# Power.net
KiCad netlist of a schematic drawn in Altium Designer
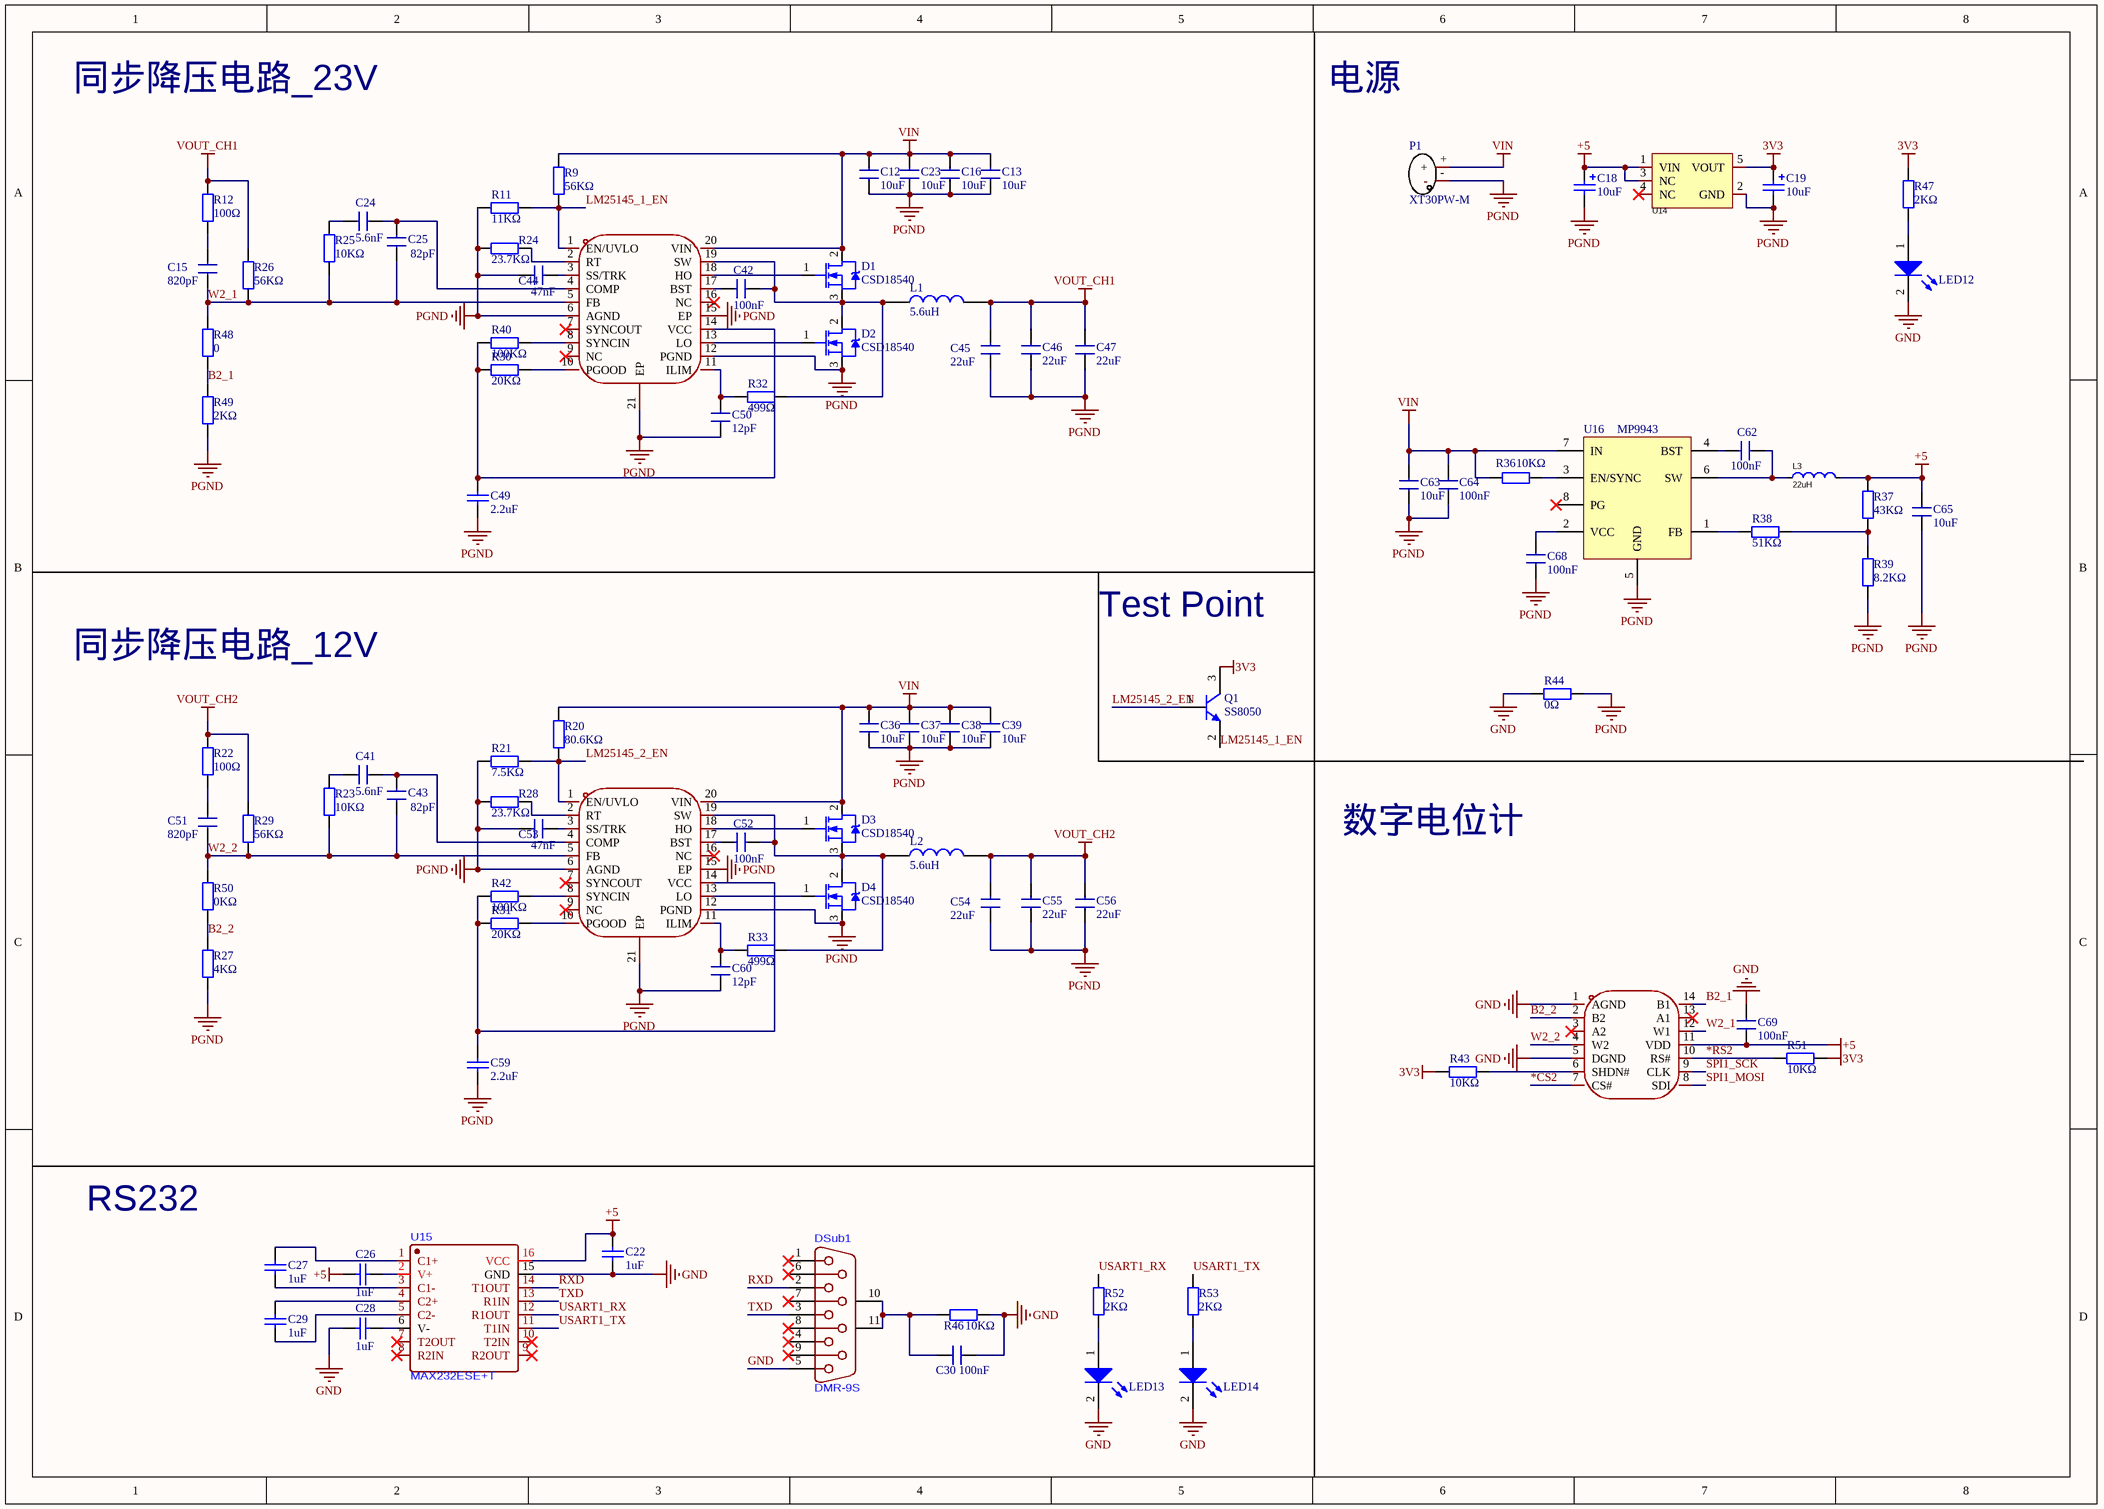
[diagram p0: Power.SchDoc]

(export (version "E")
  (design (tool "Eeschema 10.0.6"))
  (components
    (comp (ref "C12")
      (value "10uF")
      (footprint "1210")
      (description "1210贴片电容")
      (libsource (lib "Integrated_Library1") (part "1210贴片电容"))
    )
    (comp (ref "C13")
      (value "10uF")
      (footprint "1210")
      (description "1210贴片电容")
      (libsource (lib "En") (part "1210贴片电容"))
    )
    (comp (ref "C15")
      (value "820pF")
      (footprint "c0402")
      (description "贴片电容0402")
      (libsource (lib "Integrated_Library1") (part "0402贴片电容"))
    )
    (comp (ref "C16")
      (value "10uF")
      (footprint "1210")
      (description "1210贴片电容")
      (libsource (lib "En") (part "1210贴片电容"))
    )
    (comp (ref "C18")
      (value "10uF")
      (footprint "3216")
      (description "3216钽电容")
      (libsource (lib "Integrated_Library1") (part "3216钽电容"))
    )
    (comp (ref "C19")
      (value "10uF")
      (footprint "3216")
      (description "3216钽电容")
      (libsource (lib "Integrated_Library1") (part "3216钽电容"))
    )
    (comp (ref "C22")
      (value "1uF")
      (footprint "C 0603_M")
      (description "0603贴片电容")
      (libsource (lib "En") (part "0603贴片电容"))
    )
    (comp (ref "C23")
      (value "10uF")
      (footprint "1210")
      (description "1210贴片电容")
      (libsource (lib "En") (part "1210贴片电容"))
    )
    (comp (ref "C24")
      (value "5.6nF")
      (footprint "c0402")
      (description "贴片电容0402")
      (libsource (lib "Integrated_Library1") (part "0402贴片电容"))
    )
    (comp (ref "C25")
      (value "82pF")
      (footprint "c0402")
      (description "贴片电容0402")
      (libsource (lib "Integrated_Library1") (part "0402贴片电容"))
    )
    (comp (ref "C26")
      (value "1uF")
      (footprint "C 0603_M")
      (description "0603贴片电容")
      (libsource (lib "En") (part "0603贴片电容"))
    )
    (comp (ref "C27")
      (value "1uF")
      (footprint "C 0603_M")
      (description "0603贴片电容")
      (libsource (lib "En") (part "0603贴片电容"))
    )
    (comp (ref "C28")
      (value "1uF")
      (footprint "C 0603_M")
      (description "0603贴片电容")
      (libsource (lib "En") (part "0603贴片电容"))
    )
    (comp (ref "C29")
      (value "1uF")
      (footprint "C 0603_M")
      (description "0603贴片电容")
      (libsource (lib "En") (part "0603贴片电容"))
    )
    (comp (ref "C30")
      (value "100nF")
      (footprint "c0402")
      (description "贴片电容0402")
      (libsource (lib "Integrated_Library1") (part "0402贴片电容"))
    )
    (comp (ref "C36")
      (value "10uF")
      (footprint "1210")
      (description "1210贴片电容")
      (libsource (lib "Integrated_Library1") (part "1210贴片电容"))
    )
    (comp (ref "C37")
      (value "10uF")
      (footprint "1210")
      (description "1210贴片电容")
      (libsource (lib "En") (part "1210贴片电容"))
    )
    (comp (ref "C38")
      (value "10uF")
      (footprint "1210")
      (description "1210贴片电容")
      (libsource (lib "En") (part "1210贴片电容"))
    )
    (comp (ref "C39")
      (value "10uF")
      (footprint "1210")
      (description "1210贴片电容")
      (libsource (lib "En") (part "1210贴片电容"))
    )
    (comp (ref "C41")
      (value "5.6nF")
      (footprint "c0402")
      (description "贴片电容0402")
      (libsource (lib "Integrated_Library1") (part "0402贴片电容"))
    )
    (comp (ref "C42")
      (value "100nF")
      (footprint "C 0603_M")
      (description "贴片电容0402")
      (libsource (lib "Integrated_Library1") (part "0402贴片电容"))
    )
    (comp (ref "C43")
      (value "82pF")
      (footprint "c0402")
      (description "贴片电容0402")
      (libsource (lib "Integrated_Library1") (part "0402贴片电容"))
    )
    (comp (ref "C44")
      (value "47nF")
      (footprint "c0402")
      (description "贴片电容0402")
      (libsource (lib "Integrated_Library1") (part "0402贴片电容"))
    )
    (comp (ref "C45")
      (value "22uF")
      (footprint "1210")
      (description "1210贴片电容")
      (libsource (lib "En") (part "1210贴片电容"))
    )
    (comp (ref "C46")
      (value "22uF")
      (footprint "1210")
      (description "1210贴片电容")
      (libsource (lib "En") (part "1210贴片电容"))
    )
    (comp (ref "C47")
      (value "22uF")
      (footprint "1210")
      (description "1210贴片电容")
      (libsource (lib "En") (part "1210贴片电容"))
    )
    (comp (ref "C49")
      (value "2.2uF")
      (footprint "C 0603_M")
      (description "0603贴片电容")
      (libsource (lib "En") (part "0603贴片电容"))
    )
    (comp (ref "C50")
      (value "12pF")
      (footprint "c0402")
      (description "贴片电容0402")
      (libsource (lib "Integrated_Library1") (part "0402贴片电容"))
    )
    (comp (ref "C51")
      (value "820pF")
      (footprint "c0402")
      (description "贴片电容0402")
      (libsource (lib "Integrated_Library1") (part "0402贴片电容"))
    )
    (comp (ref "C52")
      (value "100nF")
      (footprint "C 0603_M")
      (description "贴片电容0402")
      (libsource (lib "Integrated_Library1") (part "0402贴片电容"))
    )
    (comp (ref "C53")
      (value "47nF")
      (footprint "c0402")
      (description "贴片电容0402")
      (libsource (lib "Integrated_Library1") (part "0402贴片电容"))
    )
    (comp (ref "C54")
      (value "22uF")
      (footprint "1210")
      (description "1210贴片电容")
      (libsource (lib "En") (part "1210贴片电容"))
    )
    (comp (ref "C55")
      (value "22uF")
      (footprint "1210")
      (description "1210贴片电容")
      (libsource (lib "En") (part "1210贴片电容"))
    )
    (comp (ref "C56")
      (value "22uF")
      (footprint "1210")
      (description "1210贴片电容")
      (libsource (lib "En") (part "1210贴片电容"))
    )
    (comp (ref "C59")
      (value "2.2uF")
      (footprint "C 0603_M")
      (description "0603贴片电容")
      (libsource (lib "En") (part "0603贴片电容"))
    )
    (comp (ref "C60")
      (value "12pF")
      (footprint "c0402")
      (description "贴片电容0402")
      (libsource (lib "Integrated_Library1") (part "0402贴片电容"))
    )
    (comp (ref "C62")
      (value "100nF")
      (footprint "c0402")
      (description "贴片电容0402")
      (libsource (lib "Integrated_Library1") (part "0402贴片电容"))
    )
    (comp (ref "C63")
      (value "10uF")
      (footprint "1210")
      (description "1210贴片电容")
      (libsource (lib "Integrated_Library1") (part "1210贴片电容"))
    )
    (comp (ref "C64")
      (value "100nF")
      (footprint "c0402")
      (description "贴片电容0402")
      (libsource (lib "Integrated_Library1") (part "0402贴片电容"))
    )
    (comp (ref "C65")
      (value "10uF")
      (footprint "1210")
      (description "1210贴片电容")
      (libsource (lib "Integrated_Library1") (part "1210贴片电容"))
    )
    (comp (ref "C68")
      (value "100nF")
      (footprint "c0402")
      (description "贴片电容0402")
      (libsource (lib "Integrated_Library1") (part "0402贴片电容"))
    )
    (comp (ref "C69")
      (value "100nF")
      (footprint "c0402")
      (description "贴片电容0402")
      (libsource (lib "Integrated_Library1") (part "0402贴片电容"))
    )
    (comp (ref "D1")
      (value "CSD18540")
      (footprint "pg-tdson-8")
      (description "N沟道MOS管")
      (fields (field (name "PUBLISHER") "Altium Limited"))
      (libsource (lib "En") (part "CSD18540"))
    )
    (comp (ref "D2")
      (value "CSD18540")
      (footprint "pg-tdson-8")
      (description "N沟道MOS管")
      (fields (field (name "PUBLISHER") "Altium Limited"))
      (libsource (lib "En") (part "CSD18540"))
    )
    (comp (ref "D3")
      (value "CSD18540")
      (footprint "pg-tdson-8")
      (description "N沟道MOS管")
      (fields (field (name "PUBLISHER") "Altium Limited"))
      (libsource (lib "En") (part "CSD18540"))
    )
    (comp (ref "D4")
      (value "CSD18540")
      (footprint "pg-tdson-8")
      (description "N沟道MOS管")
      (fields (field (name "PUBLISHER") "Altium Limited"))
      (libsource (lib "En") (part "CSD18540"))
    )
    (comp (ref "DSub1")
      (value "DMR-9S")
      (footprint "DSUB-TH_DMR-9S")
      (libsource (lib "Schlib1") (part "DMR-9S"))
    )
    (comp (ref "L1")
      (value "5.6uH")
      (footprint "L-SMD-0630")
      (description "一体成型屏蔽电感")
      (libsource (lib "En") (part "0630功率电感"))
    )
    (comp (ref "L2")
      (value "5.6uH")
      (footprint "L-SMD-0630")
      (description "一体成型屏蔽电感")
      (libsource (lib "En") (part "0630功率电感"))
    )
    (comp (ref "L3")
      (value "22uH")
      (footprint "IND-SMD_L5.4-W5.2")
      (description "一体成型屏蔽电感，0530封装，额定电流3A")
      (fields (field (name "MANUFACTURER") "XR(祥如)") (field (name "MANUFACTURER PART") "XR0530-100M"))
      (libsource (lib "En") (part "0530屏蔽电感"))
    )
    (comp (ref "LED12")
      (value "LED")
      (footprint "led0805")
      (description "0805贴片LED")
      (libsource (lib "Integrated_Library1") (part "0805贴片LED"))
    )
    (comp (ref "LED13")
      (value "LED")
      (footprint "led0805")
      (description "0805贴片LED")
      (libsource (lib "Integrated_Library1") (part "0805贴片LED"))
    )
    (comp (ref "LED14")
      (value "LED")
      (footprint "led0805")
      (description "0805贴片LED")
      (libsource (lib "Integrated_Library1") (part "0805贴片LED"))
    )
    (comp (ref "P1")
      (value "XT30PW-M")
      (footprint "XT30PW-M")
      (description "卧式XT30母头")
      (fields (field (name "PUBLISHER") "Altium Limited"))
      (libsource (lib "Integrated_Library1") (part "卧式XT30母头"))
    )
    (comp (ref "Q1")
      (value "SS8050")
      (footprint "SOT-23-3_L2.9-W1.3-P1.90-LS2.4-BR")
      (description "三极管")
      (libsource (lib "Integrated_Library1") (part "2N2222"))
    )
    (comp (ref "R9")
      (value "56KΩ")
      (footprint "R0402")
      (description "0402贴片电阻")
      (libsource (lib "") (part "0402贴片电阻_3"))
    )
    (comp (ref "R11")
      (value "11KΩ")
      (footprint "R0402")
      (description "0402贴片电阻")
      (libsource (lib "") (part "0402贴片电阻_2"))
    )
    (comp (ref "R12")
      (value "100Ω")
      (footprint "R0402")
      (description "0402贴片电阻")
      (libsource (lib "") (part "0402贴片电阻_1"))
    )
    (comp (ref "R20")
      (value "80.6KΩ")
      (footprint "R0402")
      (description "0402贴片电阻")
      (libsource (lib "") (part "0402贴片电阻_3"))
    )
    (comp (ref "R21")
      (value "7.5KΩ")
      (footprint "R0402")
      (description "0402贴片电阻")
      (libsource (lib "") (part "0402贴片电阻_2"))
    )
    (comp (ref "R22")
      (value "100Ω")
      (footprint "R0402")
      (description "0402贴片电阻")
      (libsource (lib "") (part "0402贴片电阻_1"))
    )
    (comp (ref "R23")
      (value "10KΩ")
      (footprint "R0402")
      (description "0402贴片电阻")
      (libsource (lib "") (part "0402贴片电阻_1"))
    )
    (comp (ref "R24")
      (value "23.7KΩ")
      (footprint "R0402")
      (description "0402贴片电阻")
      (libsource (lib "Integrated_Library1") (part "0402贴片电阻"))
    )
    (comp (ref "R25")
      (value "10KΩ")
      (footprint "R0402")
      (description "0402贴片电阻")
      (libsource (lib "") (part "0402贴片电阻_1"))
    )
    (comp (ref "R26")
      (value "56KΩ")
      (footprint "R0402")
      (description "0402贴片电阻")
      (libsource (lib "") (part "0402贴片电阻_1"))
    )
    (comp (ref "R27")
      (value "4KΩ")
      (footprint "R0402")
      (description "0402贴片电阻")
      (libsource (lib "") (part "0402贴片电阻_3"))
    )
    (comp (ref "R28")
      (value "23.7KΩ")
      (footprint "R0402")
      (description "0402贴片电阻")
      (libsource (lib "Integrated_Library1") (part "0402贴片电阻"))
    )
    (comp (ref "R29")
      (value "56KΩ")
      (footprint "R0402")
      (description "0402贴片电阻")
      (libsource (lib "") (part "0402贴片电阻_1"))
    )
    (comp (ref "R30")
      (value "20KΩ")
      (footprint "R0402")
      (description "0402贴片电阻")
      (libsource (lib "Integrated_Library1") (part "0402贴片电阻"))
    )
    (comp (ref "R31")
      (value "20KΩ")
      (footprint "R0402")
      (description "0402贴片电阻")
      (libsource (lib "Integrated_Library1") (part "0402贴片电阻"))
    )
    (comp (ref "R32")
      (value "499Ω")
      (footprint "R0402")
      (description "0402贴片电阻")
      (libsource (lib "Integrated_Library1") (part "0402贴片电阻"))
    )
    (comp (ref "R33")
      (value "499Ω")
      (footprint "R0402")
      (description "0402贴片电阻")
      (libsource (lib "Integrated_Library1") (part "0402贴片电阻"))
    )
    (comp (ref "R36")
      (value "10KΩ")
      (footprint "R0402")
      (description "0402贴片电阻")
      (libsource (lib "") (part "0402贴片电阻_2"))
    )
    (comp (ref "R37")
      (value "43KΩ")
      (footprint "R0402")
      (description "0402贴片电阻")
      (libsource (lib "") (part "0402贴片电阻_1"))
    )
    (comp (ref "R38")
      (value "51KΩ")
      (footprint "R0402")
      (description "0402贴片电阻")
      (libsource (lib "") (part "0402贴片电阻_2"))
    )
    (comp (ref "R39")
      (value "8.2KΩ")
      (footprint "R0402")
      (description "0402贴片电阻")
      (libsource (lib "") (part "0402贴片电阻_1"))
    )
    (comp (ref "R40")
      (value "100KΩ")
      (footprint "R0402")
      (description "0402贴片电阻")
      (libsource (lib "Integrated_Library1") (part "0402贴片电阻"))
    )
    (comp (ref "R42")
      (value "100KΩ")
      (footprint "R0402")
      (description "0402贴片电阻")
      (libsource (lib "Integrated_Library1") (part "0402贴片电阻"))
    )
    (comp (ref "R43")
      (value "10KΩ")
      (footprint "R0402")
      (description "0402贴片电阻")
      (libsource (lib "Integrated_Library1") (part "0402贴片电阻"))
    )
    (comp (ref "R44")
      (value "0Ω")
      (footprint "R0402")
      (description "0402贴片电阻")
      (libsource (lib "") (part "0402贴片电阻_2"))
    )
    (comp (ref "R46")
      (value "10KΩ")
      (footprint "R0402")
      (description "0402贴片电阻")
      (libsource (lib "") (part "0402贴片电阻_4"))
    )
    (comp (ref "R47")
      (value "2KΩ")
      (footprint "R0402")
      (description "0402贴片电阻")
      (libsource (lib "") (part "0402贴片电阻_3"))
    )
    (comp (ref "R48")
      (value "0")
      (footprint "R0402")
      (description "0402贴片电阻")
      (libsource (lib "") (part "0402贴片电阻_3"))
    )
    (comp (ref "R49")
      (value "2KΩ")
      (footprint "R0402")
      (description "0402贴片电阻")
      (libsource (lib "") (part "0402贴片电阻_3"))
    )
    (comp (ref "R50")
      (value "0KΩ")
      (footprint "R0402")
      (description "0402贴片电阻")
      (libsource (lib "") (part "0402贴片电阻_3"))
    )
    (comp (ref "R51")
      (value "10KΩ")
      (footprint "R0402")
      (description "0402贴片电阻")
      (libsource (lib "Integrated_Library1") (part "0402贴片电阻"))
    )
    (comp (ref "R52")
      (value "2KΩ")
      (footprint "R0402")
      (description "0402贴片电阻")
      (libsource (lib "") (part "0402贴片电阻_3"))
    )
    (comp (ref "R53")
      (value "2KΩ")
      (footprint "R0402")
      (description "0402贴片电阻")
      (libsource (lib "") (part "0402贴片电阻_3"))
    )
    (comp (ref "U7")
      (value "LM25145RGYR")
      (footprint "VQFN-20_L4.5-W3.5-P0.50-BL-EP")
      (fields (field (name "MANUFACTURER") "TI(德州仪器)"))
      (libsource (lib "Schlib1") (part "LM25145RGYR"))
    )
    (comp (ref "U13")
      (value "LM25145RGYR")
      (footprint "VQFN-20_L4.5-W3.5-P0.50-BL-EP")
      (fields (field (name "MANUFACTURER") "TI(德州仪器)"))
      (libsource (lib "Schlib1") (part "LM25145RGYR"))
    )
    (comp (ref "U14")
      (value "XC6201P332MR-HXY")
      (footprint "SOT-23-5_L3.0-W1.7-P0.95-LS2.8-BR")
      (description "3.3V LDO")
      (fields (field (name "MANUFACTURER") "HXY MOSFET(华轩阳电子)"))
      (libsource (lib "Integrated_Library1") (part "XC6201P332MR-HXY"))
    )
    (comp (ref "U15")
      (value "MAX232ESE+T")
      (footprint "SOIC-16_L9.9-W3.9-P1.27-LS6.0-BL")
      (libsource (lib "Schlib1") (part "MAX232ESE+T"))
    )
    (comp (ref "U16")
      (value "MP9943")
      (footprint "QFN-8 3x3")
      (libsource (lib "Integrated_Library1") (part "MP9943"))
    )
    (comp (ref "U17")
      (value "AD8402ARZ10-REEL")
      (footprint "SOIC-14_L8.7-W3.9-P1.27-LS6.0-BL")
      (fields (field (name "MANUFACTURER") "ADI(亚德诺)"))
      (libsource (lib "Schlib1") (part "AD8402ARZ10-REEL"))
    )
  )
  (nets
    (net (code "1") (name "+5") (class "Default")
      (node (ref "C18") (pin "1") (pinfunction "1_1") (pintype "passive"))
      (node (ref "C22") (pin "2") (pinfunction "2_2") (pintype "passive"))
      (node (ref "C26") (pin "2") (pinfunction "2_2") (pintype "passive"))
      (node (ref "C65") (pin "2") (pinfunction "2_2") (pintype "passive"))
      (node (ref "C69") (pin "2") (pinfunction "2_2") (pintype "passive"))
      (node (ref "L3") (pin "2") (pinfunction "2_2") (pintype "passive"))
      (node (ref "R37") (pin "2") (pinfunction "2_2") (pintype "passive"))
      (node (ref "U14") (pin "1") (pinfunction "VIN_1") (pintype "passive"))
      (node (ref "U14") (pin "3") (pinfunction "NC_3") (pintype "passive"))
      (node (ref "U15") (pin "16") (pinfunction "VCC_16") (pintype "passive"))
      (node (ref "U17") (pin "11") (pinfunction "VDD_11") (pintype "passive"))
    )
    (net (code "2") (name "/*CS2") (class "Default")
      (node (ref "U17") (pin "7") (pinfunction "CS#_7") (pintype "passive"))
    )
    (net (code "3") (name "/*RS2") (class "Default")
      (node (ref "R51") (pin "2") (pinfunction "2_2") (pintype "passive"))
      (node (ref "U17") (pin "10") (pinfunction "RS#_10") (pintype "passive"))
    )
    (net (code "4") (name "/B2_1") (class "Default")
      (node (ref "R48") (pin "2") (pinfunction "2_2") (pintype "passive"))
      (node (ref "R49") (pin "1") (pinfunction "1_1") (pintype "passive"))
      (node (ref "U17") (pin "14") (pinfunction "B1_14") (pintype "passive"))
    )
    (net (code "5") (name "/B2_2") (class "Default")
      (node (ref "R27") (pin "1") (pinfunction "1_1") (pintype "passive"))
      (node (ref "R50") (pin "2") (pinfunction "2_2") (pintype "passive"))
      (node (ref "U17") (pin "2") (pinfunction "B2_2") (pintype "passive"))
    )
    (net (code "6") (name "/LM25145_1_EN") (class "Default")
      (node (ref "Q1") (pin "2") (pinfunction "E_2") (pintype "passive"))
      (node (ref "R11") (pin "2") (pinfunction "2_2") (pintype "passive"))
      (node (ref "R9") (pin "2") (pinfunction "2_2") (pintype "passive"))
      (node (ref "U13") (pin "1") (pinfunction "EN/UVLO_1") (pintype "passive"))
    )
    (net (code "7") (name "/LM25145_2_EN") (class "Default")
      (node (ref "Q1") (pin "1") (pinfunction "B_1") (pintype "passive"))
      (node (ref "R20") (pin "2") (pinfunction "2_2") (pintype "passive"))
      (node (ref "R21") (pin "2") (pinfunction "2_2") (pintype "passive"))
      (node (ref "U7") (pin "1") (pinfunction "EN/UVLO_1") (pintype "passive"))
    )
    (net (code "8") (name "/RXD") (class "Default")
      (node (ref "DSub1") (pin "2") (pinfunction "2_2") (pintype "passive"))
      (node (ref "U15") (pin "14") (pinfunction "T1OUT_14") (pintype "passive"))
    )
    (net (code "9") (name "/SPI1_MOSI") (class "Default")
      (node (ref "U17") (pin "8") (pinfunction "SDI_8") (pintype "passive"))
    )
    (net (code "10") (name "/SPI1_SCK") (class "Default")
      (node (ref "U17") (pin "9") (pinfunction "CLK_9") (pintype "passive"))
    )
    (net (code "11") (name "/TXD") (class "Default")
      (node (ref "DSub1") (pin "3") (pinfunction "3_3") (pintype "passive"))
      (node (ref "U15") (pin "13") (pinfunction "R1IN_13") (pintype "passive"))
    )
    (net (code "12") (name "/USART1_RX") (class "Default")
      (node (ref "R52") (pin "1") (pinfunction "1_1") (pintype "passive"))
      (node (ref "U15") (pin "12") (pinfunction "R1OUT_12") (pintype "passive"))
    )
    (net (code "13") (name "/USART1_TX") (class "Default")
      (node (ref "R53") (pin "1") (pinfunction "1_1") (pintype "passive"))
      (node (ref "U15") (pin "11") (pinfunction "T1IN_11") (pintype "passive"))
    )
    (net (code "14") (name "/W2_1") (class "Default")
      (node (ref "C15") (pin "2") (pinfunction "2_2") (pintype "passive"))
      (node (ref "C25") (pin "1") (pinfunction "1_1") (pintype "passive"))
      (node (ref "R25") (pin "1") (pinfunction "1_1") (pintype "passive"))
      (node (ref "R26") (pin "1") (pinfunction "1_1") (pintype "passive"))
      (node (ref "R48") (pin "1") (pinfunction "1_1") (pintype "passive"))
      (node (ref "U13") (pin "5") (pinfunction "FB_5") (pintype "passive"))
      (node (ref "U17") (pin "12") (pinfunction "W1_12") (pintype "passive"))
    )
    (net (code "15") (name "/W2_2") (class "Default")
      (node (ref "C43") (pin "1") (pinfunction "1_1") (pintype "passive"))
      (node (ref "C51") (pin "2") (pinfunction "2_2") (pintype "passive"))
      (node (ref "R23") (pin "1") (pinfunction "1_1") (pintype "passive"))
      (node (ref "R29") (pin "1") (pinfunction "1_1") (pintype "passive"))
      (node (ref "R50") (pin "1") (pinfunction "1_1") (pintype "passive"))
      (node (ref "U17") (pin "4") (pinfunction "W2_4") (pintype "passive"))
      (node (ref "U7") (pin "5") (pinfunction "FB_5") (pintype "passive"))
    )
    (net (code "16") (name "3V3") (class "Default")
      (node (ref "C19") (pin "1") (pinfunction "1_1") (pintype "passive"))
      (node (ref "Q1") (pin "3") (pinfunction "C_3") (pintype "passive"))
      (node (ref "R43") (pin "2") (pinfunction "2_2") (pintype "passive"))
      (node (ref "R47") (pin "1") (pinfunction "1_1") (pintype "passive"))
      (node (ref "R51") (pin "1") (pinfunction "1_1") (pintype "passive"))
      (node (ref "U14") (pin "5") (pinfunction "VOUT_5") (pintype "passive"))
    )
    (net (code "17") (name "GND") (class "Default")
      (node (ref "C22") (pin "1") (pinfunction "1_1") (pintype "passive"))
      (node (ref "C28") (pin "2") (pinfunction "2_2") (pintype "passive"))
      (node (ref "C30") (pin "2") (pinfunction "2_2") (pintype "passive"))
      (node (ref "C69") (pin "1") (pinfunction "1_1") (pintype "passive"))
      (node (ref "DSub1") (pin "5") (pinfunction "5_5") (pintype "passive"))
      (node (ref "LED12") (pin "2") (pinfunction "K_2") (pintype "passive"))
      (node (ref "LED13") (pin "2") (pinfunction "K_2") (pintype "passive"))
      (node (ref "LED14") (pin "2") (pinfunction "K_2") (pintype "passive"))
      (node (ref "R44") (pin "1") (pinfunction "1_1") (pintype "passive"))
      (node (ref "R46") (pin "2") (pinfunction "2_2") (pintype "passive"))
      (node (ref "U15") (pin "15") (pinfunction "GND_15") (pintype "passive"))
      (node (ref "U17") (pin "1") (pinfunction "AGND_1") (pintype "passive"))
      (node (ref "U17") (pin "5") (pinfunction "DGND_5") (pintype "passive"))
    )
    (net (code "18") (name "Net-(C15-Pad1)") (class "Default")
      (node (ref "C15") (pin "1") (pinfunction "1_1") (pintype "passive"))
      (node (ref "R12") (pin "1") (pinfunction "1_1") (pintype "passive"))
    )
    (net (code "19") (name "Net-(C24-Pad2)") (class "Default")
      (node (ref "C24") (pin "2") (pinfunction "2_2") (pintype "passive"))
      (node (ref "R25") (pin "2") (pinfunction "2_2") (pintype "passive"))
    )
    (net (code "20") (name "Net-(C41-Pad2)") (class "Default")
      (node (ref "C41") (pin "2") (pinfunction "2_2") (pintype "passive"))
      (node (ref "R23") (pin "2") (pinfunction "2_2") (pintype "passive"))
    )
    (net (code "21") (name "Net-(C51-Pad1)") (class "Default")
      (node (ref "C51") (pin "1") (pinfunction "1_1") (pintype "passive"))
      (node (ref "R22") (pin "1") (pinfunction "1_1") (pintype "passive"))
    )
    (net (code "22") (name "Net-(D1-G)") (class "Default")
      (node (ref "D1") (pin "1") (pinfunction "G_1") (pintype "passive"))
      (node (ref "U13") (pin "18") (pinfunction "HO_18") (pintype "passive"))
    )
    (net (code "23") (name "Net-(D1-S)") (class "Default")
      (node (ref "C42") (pin "1") (pinfunction "1_1") (pintype "passive"))
      (node (ref "D1") (pin "3") (pinfunction "S_3") (pintype "passive"))
      (node (ref "D2") (pin "2") (pinfunction "D_2") (pintype "passive"))
      (node (ref "L1") (pin "1") (pinfunction "1_1") (pintype "passive"))
      (node (ref "R32") (pin "1") (pinfunction "1_1") (pintype "passive"))
      (node (ref "U13") (pin "19") (pinfunction "SW_19") (pintype "passive"))
    )
    (net (code "24") (name "Net-(D2-G)") (class "Default")
      (node (ref "D2") (pin "1") (pinfunction "G_1") (pintype "passive"))
      (node (ref "U13") (pin "13") (pinfunction "LO_13") (pintype "passive"))
    )
    (net (code "25") (name "Net-(D3-G)") (class "Default")
      (node (ref "D3") (pin "1") (pinfunction "G_1") (pintype "passive"))
      (node (ref "U7") (pin "18") (pinfunction "HO_18") (pintype "passive"))
    )
    (net (code "26") (name "Net-(D3-S)") (class "Default")
      (node (ref "C52") (pin "1") (pinfunction "1_1") (pintype "passive"))
      (node (ref "D3") (pin "3") (pinfunction "S_3") (pintype "passive"))
      (node (ref "D4") (pin "2") (pinfunction "D_2") (pintype "passive"))
      (node (ref "L2") (pin "1") (pinfunction "1_1") (pintype "passive"))
      (node (ref "R33") (pin "1") (pinfunction "1_1") (pintype "passive"))
      (node (ref "U7") (pin "19") (pinfunction "SW_19") (pintype "passive"))
    )
    (net (code "27") (name "Net-(D4-G)") (class "Default")
      (node (ref "D4") (pin "1") (pinfunction "G_1") (pintype "passive"))
      (node (ref "U7") (pin "13") (pinfunction "LO_13") (pintype "passive"))
    )
    (net (code "28") (name "Net-(DSub1-MH1)") (class "Default")
      (node (ref "C30") (pin "1") (pinfunction "1_1") (pintype "passive"))
      (node (ref "DSub1") (pin "10") (pinfunction "MH1_10") (pintype "passive"))
      (node (ref "DSub1") (pin "11") (pinfunction "MH2_11") (pintype "passive"))
      (node (ref "R46") (pin "1") (pinfunction "1_1") (pintype "passive"))
    )
    (net (code "29") (name "Net-(LED12-A)") (class "Default")
      (node (ref "LED12") (pin "1") (pinfunction "A_1") (pintype "passive"))
      (node (ref "R47") (pin "2") (pinfunction "2_2") (pintype "passive"))
    )
    (net (code "30") (name "Net-(LED13-A)") (class "Default")
      (node (ref "LED13") (pin "1") (pinfunction "A_1") (pintype "passive"))
      (node (ref "R52") (pin "2") (pinfunction "2_2") (pintype "passive"))
    )
    (net (code "31") (name "Net-(LED14-A)") (class "Default")
      (node (ref "LED14") (pin "1") (pinfunction "A_1") (pintype "passive"))
      (node (ref "R53") (pin "2") (pinfunction "2_2") (pintype "passive"))
    )
    (net (code "32") (name "Net-(R37-Pad1)") (class "Default")
      (node (ref "R37") (pin "1") (pinfunction "1_1") (pintype "passive"))
      (node (ref "R38") (pin "2") (pinfunction "2_2") (pintype "passive"))
      (node (ref "R39") (pin "2") (pinfunction "2_2") (pintype "passive"))
    )
    (net (code "33") (name "Net-(U7-BST)") (class "Default")
      (node (ref "C52") (pin "2") (pinfunction "2_2") (pintype "passive"))
      (node (ref "U7") (pin "17") (pinfunction "BST_17") (pintype "passive"))
    )
    (net (code "34") (name "Net-(U7-COMP)") (class "Default")
      (node (ref "C41") (pin "1") (pinfunction "1_1") (pintype "passive"))
      (node (ref "C43") (pin "2") (pinfunction "2_2") (pintype "passive"))
      (node (ref "U7") (pin "4") (pinfunction "COMP_4") (pintype "passive"))
    )
    (net (code "35") (name "Net-(U7-ILIM)") (class "Default")
      (node (ref "C60") (pin "2") (pinfunction "2_2") (pintype "passive"))
      (node (ref "R33") (pin "2") (pinfunction "2_2") (pintype "passive"))
      (node (ref "U7") (pin "11") (pinfunction "ILIM_11") (pintype "passive"))
    )
    (net (code "36") (name "Net-(U7-PGOOD)") (class "Default")
      (node (ref "R31") (pin "1") (pinfunction "1_1") (pintype "passive"))
      (node (ref "U7") (pin "10") (pinfunction "PGOOD_10") (pintype "passive"))
    )
    (net (code "37") (name "Net-(U7-RT)") (class "Default")
      (node (ref "R28") (pin "1") (pinfunction "1_1") (pintype "passive"))
      (node (ref "U7") (pin "2") (pinfunction "RT_2") (pintype "passive"))
    )
    (net (code "38") (name "Net-(U7-SS{slash}TRK)") (class "Default")
      (node (ref "C53") (pin "1") (pinfunction "1_1") (pintype "passive"))
      (node (ref "U7") (pin "3") (pinfunction "SS/TRK_3") (pintype "passive"))
    )
    (net (code "39") (name "Net-(U7-SYNCIN)") (class "Default")
      (node (ref "R42") (pin "1") (pinfunction "1_1") (pintype "passive"))
      (node (ref "U7") (pin "8") (pinfunction "SYNCIN_8") (pintype "passive"))
    )
    (net (code "40") (name "Net-(U7-VCC)") (class "Default")
      (node (ref "C59") (pin "2") (pinfunction "2_2") (pintype "passive"))
      (node (ref "R31") (pin "2") (pinfunction "2_2") (pintype "passive"))
      (node (ref "R42") (pin "2") (pinfunction "2_2") (pintype "passive"))
      (node (ref "U7") (pin "14") (pinfunction "VCC_14") (pintype "passive"))
    )
    (net (code "41") (name "Net-(U13-BST)") (class "Default")
      (node (ref "C42") (pin "2") (pinfunction "2_2") (pintype "passive"))
      (node (ref "U13") (pin "17") (pinfunction "BST_17") (pintype "passive"))
    )
    (net (code "42") (name "Net-(U13-COMP)") (class "Default")
      (node (ref "C24") (pin "1") (pinfunction "1_1") (pintype "passive"))
      (node (ref "C25") (pin "2") (pinfunction "2_2") (pintype "passive"))
      (node (ref "U13") (pin "4") (pinfunction "COMP_4") (pintype "passive"))
    )
    (net (code "43") (name "Net-(U13-ILIM)") (class "Default")
      (node (ref "C50") (pin "2") (pinfunction "2_2") (pintype "passive"))
      (node (ref "R32") (pin "2") (pinfunction "2_2") (pintype "passive"))
      (node (ref "U13") (pin "11") (pinfunction "ILIM_11") (pintype "passive"))
    )
    (net (code "44") (name "Net-(U13-PGOOD)") (class "Default")
      (node (ref "R30") (pin "1") (pinfunction "1_1") (pintype "passive"))
      (node (ref "U13") (pin "10") (pinfunction "PGOOD_10") (pintype "passive"))
    )
    (net (code "45") (name "Net-(U13-RT)") (class "Default")
      (node (ref "R24") (pin "1") (pinfunction "1_1") (pintype "passive"))
      (node (ref "U13") (pin "2") (pinfunction "RT_2") (pintype "passive"))
    )
    (net (code "46") (name "Net-(U13-SS{slash}TRK)") (class "Default")
      (node (ref "C44") (pin "1") (pinfunction "1_1") (pintype "passive"))
      (node (ref "U13") (pin "3") (pinfunction "SS/TRK_3") (pintype "passive"))
    )
    (net (code "47") (name "Net-(U13-SYNCIN)") (class "Default")
      (node (ref "R40") (pin "1") (pinfunction "1_1") (pintype "passive"))
      (node (ref "U13") (pin "8") (pinfunction "SYNCIN_8") (pintype "passive"))
    )
    (net (code "48") (name "Net-(U13-VCC)") (class "Default")
      (node (ref "C49") (pin "2") (pinfunction "2_2") (pintype "passive"))
      (node (ref "R30") (pin "2") (pinfunction "2_2") (pintype "passive"))
      (node (ref "R40") (pin "2") (pinfunction "2_2") (pintype "passive"))
      (node (ref "U13") (pin "14") (pinfunction "VCC_14") (pintype "passive"))
    )
    (net (code "49") (name "Net-(U15-C1+)") (class "Default")
      (node (ref "C27") (pin "1") (pinfunction "1_1") (pintype "passive"))
      (node (ref "U15") (pin "1") (pinfunction "C1+_1") (pintype "passive"))
    )
    (net (code "50") (name "Net-(U15-C1-)") (class "Default")
      (node (ref "C27") (pin "2") (pinfunction "2_2") (pintype "passive"))
      (node (ref "U15") (pin "3") (pinfunction "C1-_3") (pintype "passive"))
    )
    (net (code "51") (name "Net-(U15-C2+)") (class "Default")
      (node (ref "C29") (pin "1") (pinfunction "1_1") (pintype "passive"))
      (node (ref "U15") (pin "4") (pinfunction "C2+_4") (pintype "passive"))
    )
    (net (code "52") (name "Net-(U15-C2-)") (class "Default")
      (node (ref "C29") (pin "2") (pinfunction "2_2") (pintype "passive"))
      (node (ref "U15") (pin "5") (pinfunction "C2-_5") (pintype "passive"))
    )
    (net (code "53") (name "Net-(U15-V+)") (class "Default")
      (node (ref "C26") (pin "1") (pinfunction "1_1") (pintype "passive"))
      (node (ref "U15") (pin "2") (pinfunction "V+_2") (pintype "passive"))
    )
    (net (code "54") (name "Net-(U15-V-)") (class "Default")
      (node (ref "C28") (pin "1") (pinfunction "1_1") (pintype "passive"))
      (node (ref "U15") (pin "6") (pinfunction "V-_6") (pintype "passive"))
    )
    (net (code "55") (name "Net-(U16-BST)") (class "Default")
      (node (ref "C62") (pin "1") (pinfunction "1_1") (pintype "passive"))
      (node (ref "U16") (pin "4") (pinfunction "BST_4") (pintype "passive"))
    )
    (net (code "56") (name "Net-(U16-EN{slash}SYNC)") (class "Default")
      (node (ref "R36") (pin "2") (pinfunction "2_2") (pintype "passive"))
      (node (ref "U16") (pin "3") (pinfunction "EN/SYNC_3") (pintype "passive"))
    )
    (net (code "57") (name "Net-(U16-FB)") (class "Default")
      (node (ref "R38") (pin "1") (pinfunction "1_1") (pintype "passive"))
      (node (ref "U16") (pin "1") (pinfunction "FB_1") (pintype "passive"))
    )
    (net (code "58") (name "Net-(U16-SW)") (class "Default")
      (node (ref "C62") (pin "2") (pinfunction "2_2") (pintype "passive"))
      (node (ref "L3") (pin "1") (pinfunction "1_1") (pintype "passive"))
      (node (ref "U16") (pin "6") (pinfunction "SW_6") (pintype "passive"))
    )
    (net (code "59") (name "Net-(U16-VCC)") (class "Default")
      (node (ref "C68") (pin "2") (pinfunction "2_2") (pintype "passive"))
      (node (ref "U16") (pin "2") (pinfunction "VCC_2") (pintype "passive"))
    )
    (net (code "60") (name "Net-(U17-SHDN#)") (class "Default")
      (node (ref "R43") (pin "1") (pinfunction "1_1") (pintype "passive"))
      (node (ref "U17") (pin "6") (pinfunction "SHDN#_6") (pintype "passive"))
    )
    (net (code "61") (name "PGND") (class "Default")
      (node (ref "C12") (pin "1") (pinfunction "1_1") (pintype "passive"))
      (node (ref "C13") (pin "1") (pinfunction "1_1") (pintype "passive"))
      (node (ref "C16") (pin "1") (pinfunction "1_1") (pintype "passive"))
      (node (ref "C18") (pin "2") (pinfunction "2_2") (pintype "passive"))
      (node (ref "C19") (pin "2") (pinfunction "2_2") (pintype "passive"))
      (node (ref "C23") (pin "1") (pinfunction "1_1") (pintype "passive"))
      (node (ref "C36") (pin "1") (pinfunction "1_1") (pintype "passive"))
      (node (ref "C37") (pin "1") (pinfunction "1_1") (pintype "passive"))
      (node (ref "C38") (pin "1") (pinfunction "1_1") (pintype "passive"))
      (node (ref "C39") (pin "1") (pinfunction "1_1") (pintype "passive"))
      (node (ref "C44") (pin "2") (pinfunction "2_2") (pintype "passive"))
      (node (ref "C45") (pin "1") (pinfunction "1_1") (pintype "passive"))
      (node (ref "C46") (pin "1") (pinfunction "1_1") (pintype "passive"))
      (node (ref "C47") (pin "1") (pinfunction "1_1") (pintype "passive"))
      (node (ref "C49") (pin "1") (pinfunction "1_1") (pintype "passive"))
      (node (ref "C50") (pin "1") (pinfunction "1_1") (pintype "passive"))
      (node (ref "C53") (pin "2") (pinfunction "2_2") (pintype "passive"))
      (node (ref "C54") (pin "1") (pinfunction "1_1") (pintype "passive"))
      (node (ref "C55") (pin "1") (pinfunction "1_1") (pintype "passive"))
      (node (ref "C56") (pin "1") (pinfunction "1_1") (pintype "passive"))
      (node (ref "C59") (pin "1") (pinfunction "1_1") (pintype "passive"))
      (node (ref "C60") (pin "1") (pinfunction "1_1") (pintype "passive"))
      (node (ref "C63") (pin "1") (pinfunction "1_1") (pintype "passive"))
      (node (ref "C64") (pin "1") (pinfunction "1_1") (pintype "passive"))
      (node (ref "C65") (pin "1") (pinfunction "1_1") (pintype "passive"))
      (node (ref "C68") (pin "1") (pinfunction "1_1") (pintype "passive"))
      (node (ref "D2") (pin "3") (pinfunction "S_3") (pintype "passive"))
      (node (ref "D4") (pin "3") (pinfunction "S_3") (pintype "passive"))
      (node (ref "P1") (pin "-") (pinfunction "-_-") (pintype "passive"))
      (node (ref "R11") (pin "1") (pinfunction "1_1") (pintype "passive"))
      (node (ref "R21") (pin "1") (pinfunction "1_1") (pintype "passive"))
      (node (ref "R24") (pin "2") (pinfunction "2_2") (pintype "passive"))
      (node (ref "R27") (pin "2") (pinfunction "2_2") (pintype "passive"))
      (node (ref "R28") (pin "2") (pinfunction "2_2") (pintype "passive"))
      (node (ref "R39") (pin "1") (pinfunction "1_1") (pintype "passive"))
      (node (ref "R44") (pin "2") (pinfunction "2_2") (pintype "passive"))
      (node (ref "R49") (pin "2") (pinfunction "2_2") (pintype "passive"))
      (node (ref "U13") (pin "12") (pinfunction "PGND_12") (pintype "passive"))
      (node (ref "U13") (pin "15") (pinfunction "EP_15") (pintype "passive"))
      (node (ref "U13") (pin "21") (pinfunction "EP_21") (pintype "passive"))
      (node (ref "U13") (pin "6") (pinfunction "AGND_6") (pintype "passive"))
      (node (ref "U14") (pin "2") (pinfunction "GND_2") (pintype "passive"))
      (node (ref "U16") (pin "5") (pinfunction "GND_5") (pintype "passive"))
      (node (ref "U7") (pin "12") (pinfunction "PGND_12") (pintype "passive"))
      (node (ref "U7") (pin "15") (pinfunction "EP_15") (pintype "passive"))
      (node (ref "U7") (pin "21") (pinfunction "EP_21") (pintype "passive"))
      (node (ref "U7") (pin "6") (pinfunction "AGND_6") (pintype "passive"))
    )
    (net (code "62") (name "VIN") (class "Default")
      (node (ref "C12") (pin "2") (pinfunction "2_2") (pintype "passive"))
      (node (ref "C13") (pin "2") (pinfunction "2_2") (pintype "passive"))
      (node (ref "C16") (pin "2") (pinfunction "2_2") (pintype "passive"))
      (node (ref "C23") (pin "2") (pinfunction "2_2") (pintype "passive"))
      (node (ref "C36") (pin "2") (pinfunction "2_2") (pintype "passive"))
      (node (ref "C37") (pin "2") (pinfunction "2_2") (pintype "passive"))
      (node (ref "C38") (pin "2") (pinfunction "2_2") (pintype "passive"))
      (node (ref "C39") (pin "2") (pinfunction "2_2") (pintype "passive"))
      (node (ref "C63") (pin "2") (pinfunction "2_2") (pintype "passive"))
      (node (ref "C64") (pin "2") (pinfunction "2_2") (pintype "passive"))
      (node (ref "D1") (pin "2") (pinfunction "D_2") (pintype "passive"))
      (node (ref "D3") (pin "2") (pinfunction "D_2") (pintype "passive"))
      (node (ref "P1") (pin "+") (pinfunction "+_+") (pintype "passive"))
      (node (ref "R20") (pin "1") (pinfunction "1_1") (pintype "passive"))
      (node (ref "R36") (pin "1") (pinfunction "1_1") (pintype "passive"))
      (node (ref "R9") (pin "1") (pinfunction "1_1") (pintype "passive"))
      (node (ref "U13") (pin "20") (pinfunction "VIN_20") (pintype "passive"))
      (node (ref "U16") (pin "7") (pinfunction "IN_7") (pintype "passive"))
      (node (ref "U7") (pin "20") (pinfunction "VIN_20") (pintype "passive"))
    )
    (net (code "63") (name "VOUT_CH1") (class "Default")
      (node (ref "C45") (pin "2") (pinfunction "2_2") (pintype "passive"))
      (node (ref "C46") (pin "2") (pinfunction "2_2") (pintype "passive"))
      (node (ref "C47") (pin "2") (pinfunction "2_2") (pintype "passive"))
      (node (ref "L1") (pin "2") (pinfunction "2_2") (pintype "passive"))
      (node (ref "R12") (pin "2") (pinfunction "2_2") (pintype "passive"))
      (node (ref "R26") (pin "2") (pinfunction "2_2") (pintype "passive"))
    )
    (net (code "64") (name "VOUT_CH2") (class "Default")
      (node (ref "C54") (pin "2") (pinfunction "2_2") (pintype "passive"))
      (node (ref "C55") (pin "2") (pinfunction "2_2") (pintype "passive"))
      (node (ref "C56") (pin "2") (pinfunction "2_2") (pintype "passive"))
      (node (ref "L2") (pin "2") (pinfunction "2_2") (pintype "passive"))
      (node (ref "R22") (pin "2") (pinfunction "2_2") (pintype "passive"))
      (node (ref "R29") (pin "2") (pinfunction "2_2") (pintype "passive"))
    )
    (net (code "65") (name "unconnected-(DSub1-Pad1)") (class "Default")
      (node (ref "DSub1") (pin "1") (pinfunction "1_1") (pintype "passive+no_connect"))
    )
    (net (code "66") (name "unconnected-(DSub1-Pad4)") (class "Default")
      (node (ref "DSub1") (pin "4") (pinfunction "4_4") (pintype "passive+no_connect"))
    )
    (net (code "67") (name "unconnected-(DSub1-Pad6)") (class "Default")
      (node (ref "DSub1") (pin "6") (pinfunction "6_6") (pintype "passive+no_connect"))
    )
    (net (code "68") (name "unconnected-(DSub1-Pad7)") (class "Default")
      (node (ref "DSub1") (pin "7") (pinfunction "7_7") (pintype "passive+no_connect"))
    )
    (net (code "69") (name "unconnected-(DSub1-Pad8)") (class "Default")
      (node (ref "DSub1") (pin "8") (pinfunction "8_8") (pintype "passive+no_connect"))
    )
    (net (code "70") (name "unconnected-(DSub1-Pad9)") (class "Default")
      (node (ref "DSub1") (pin "9") (pinfunction "9_9") (pintype "passive+no_connect"))
    )
    (net (code "71") (name "unconnected-(U7-NC-Pad9)") (class "Default")
      (node (ref "U7") (pin "9") (pinfunction "NC_9") (pintype "passive+no_connect"))
    )
    (net (code "72") (name "unconnected-(U7-NC-Pad16)") (class "Default")
      (node (ref "U7") (pin "16") (pinfunction "NC_16") (pintype "passive+no_connect"))
    )
    (net (code "73") (name "unconnected-(U7-SYNCOUT-Pad7)") (class "Default")
      (node (ref "U7") (pin "7") (pinfunction "SYNCOUT_7") (pintype "passive+no_connect"))
    )
    (net (code "74") (name "unconnected-(U13-NC-Pad9)") (class "Default")
      (node (ref "U13") (pin "9") (pinfunction "NC_9") (pintype "passive+no_connect"))
    )
    (net (code "75") (name "unconnected-(U13-NC-Pad16)") (class "Default")
      (node (ref "U13") (pin "16") (pinfunction "NC_16") (pintype "passive+no_connect"))
    )
    (net (code "76") (name "unconnected-(U13-SYNCOUT-Pad7)") (class "Default")
      (node (ref "U13") (pin "7") (pinfunction "SYNCOUT_7") (pintype "passive+no_connect"))
    )
    (net (code "77") (name "unconnected-(U14-NC-Pad4)") (class "Default")
      (node (ref "U14") (pin "4") (pinfunction "NC_4") (pintype "passive+no_connect"))
    )
    (net (code "78") (name "unconnected-(U15-R2IN-Pad8)") (class "Default")
      (node (ref "U15") (pin "8") (pinfunction "R2IN_8") (pintype "passive+no_connect"))
    )
    (net (code "79") (name "unconnected-(U15-R2OUT-Pad9)") (class "Default")
      (node (ref "U15") (pin "9") (pinfunction "R2OUT_9") (pintype "passive+no_connect"))
    )
    (net (code "80") (name "unconnected-(U15-T2IN-Pad10)") (class "Default")
      (node (ref "U15") (pin "10") (pinfunction "T2IN_10") (pintype "passive+no_connect"))
    )
    (net (code "81") (name "unconnected-(U15-T2OUT-Pad7)") (class "Default")
      (node (ref "U15") (pin "7") (pinfunction "T2OUT_7") (pintype "passive+no_connect"))
    )
    (net (code "82") (name "unconnected-(U16-PG-Pad8)") (class "Default")
      (node (ref "U16") (pin "8") (pinfunction "PG_8") (pintype "passive+no_connect"))
    )
    (net (code "83") (name "unconnected-(U17-A1-Pad13)") (class "Default")
      (node (ref "U17") (pin "13") (pinfunction "A1_13") (pintype "passive+no_connect"))
    )
    (net (code "84") (name "unconnected-(U17-A2-Pad3)") (class "Default")
      (node (ref "U17") (pin "3") (pinfunction "A2_3") (pintype "passive+no_connect"))
    )
  )
)
